# SCH_Flight-Computer-V5_2024-08-18.net
KiCad netlist of a schematic drawn in EasyEDA
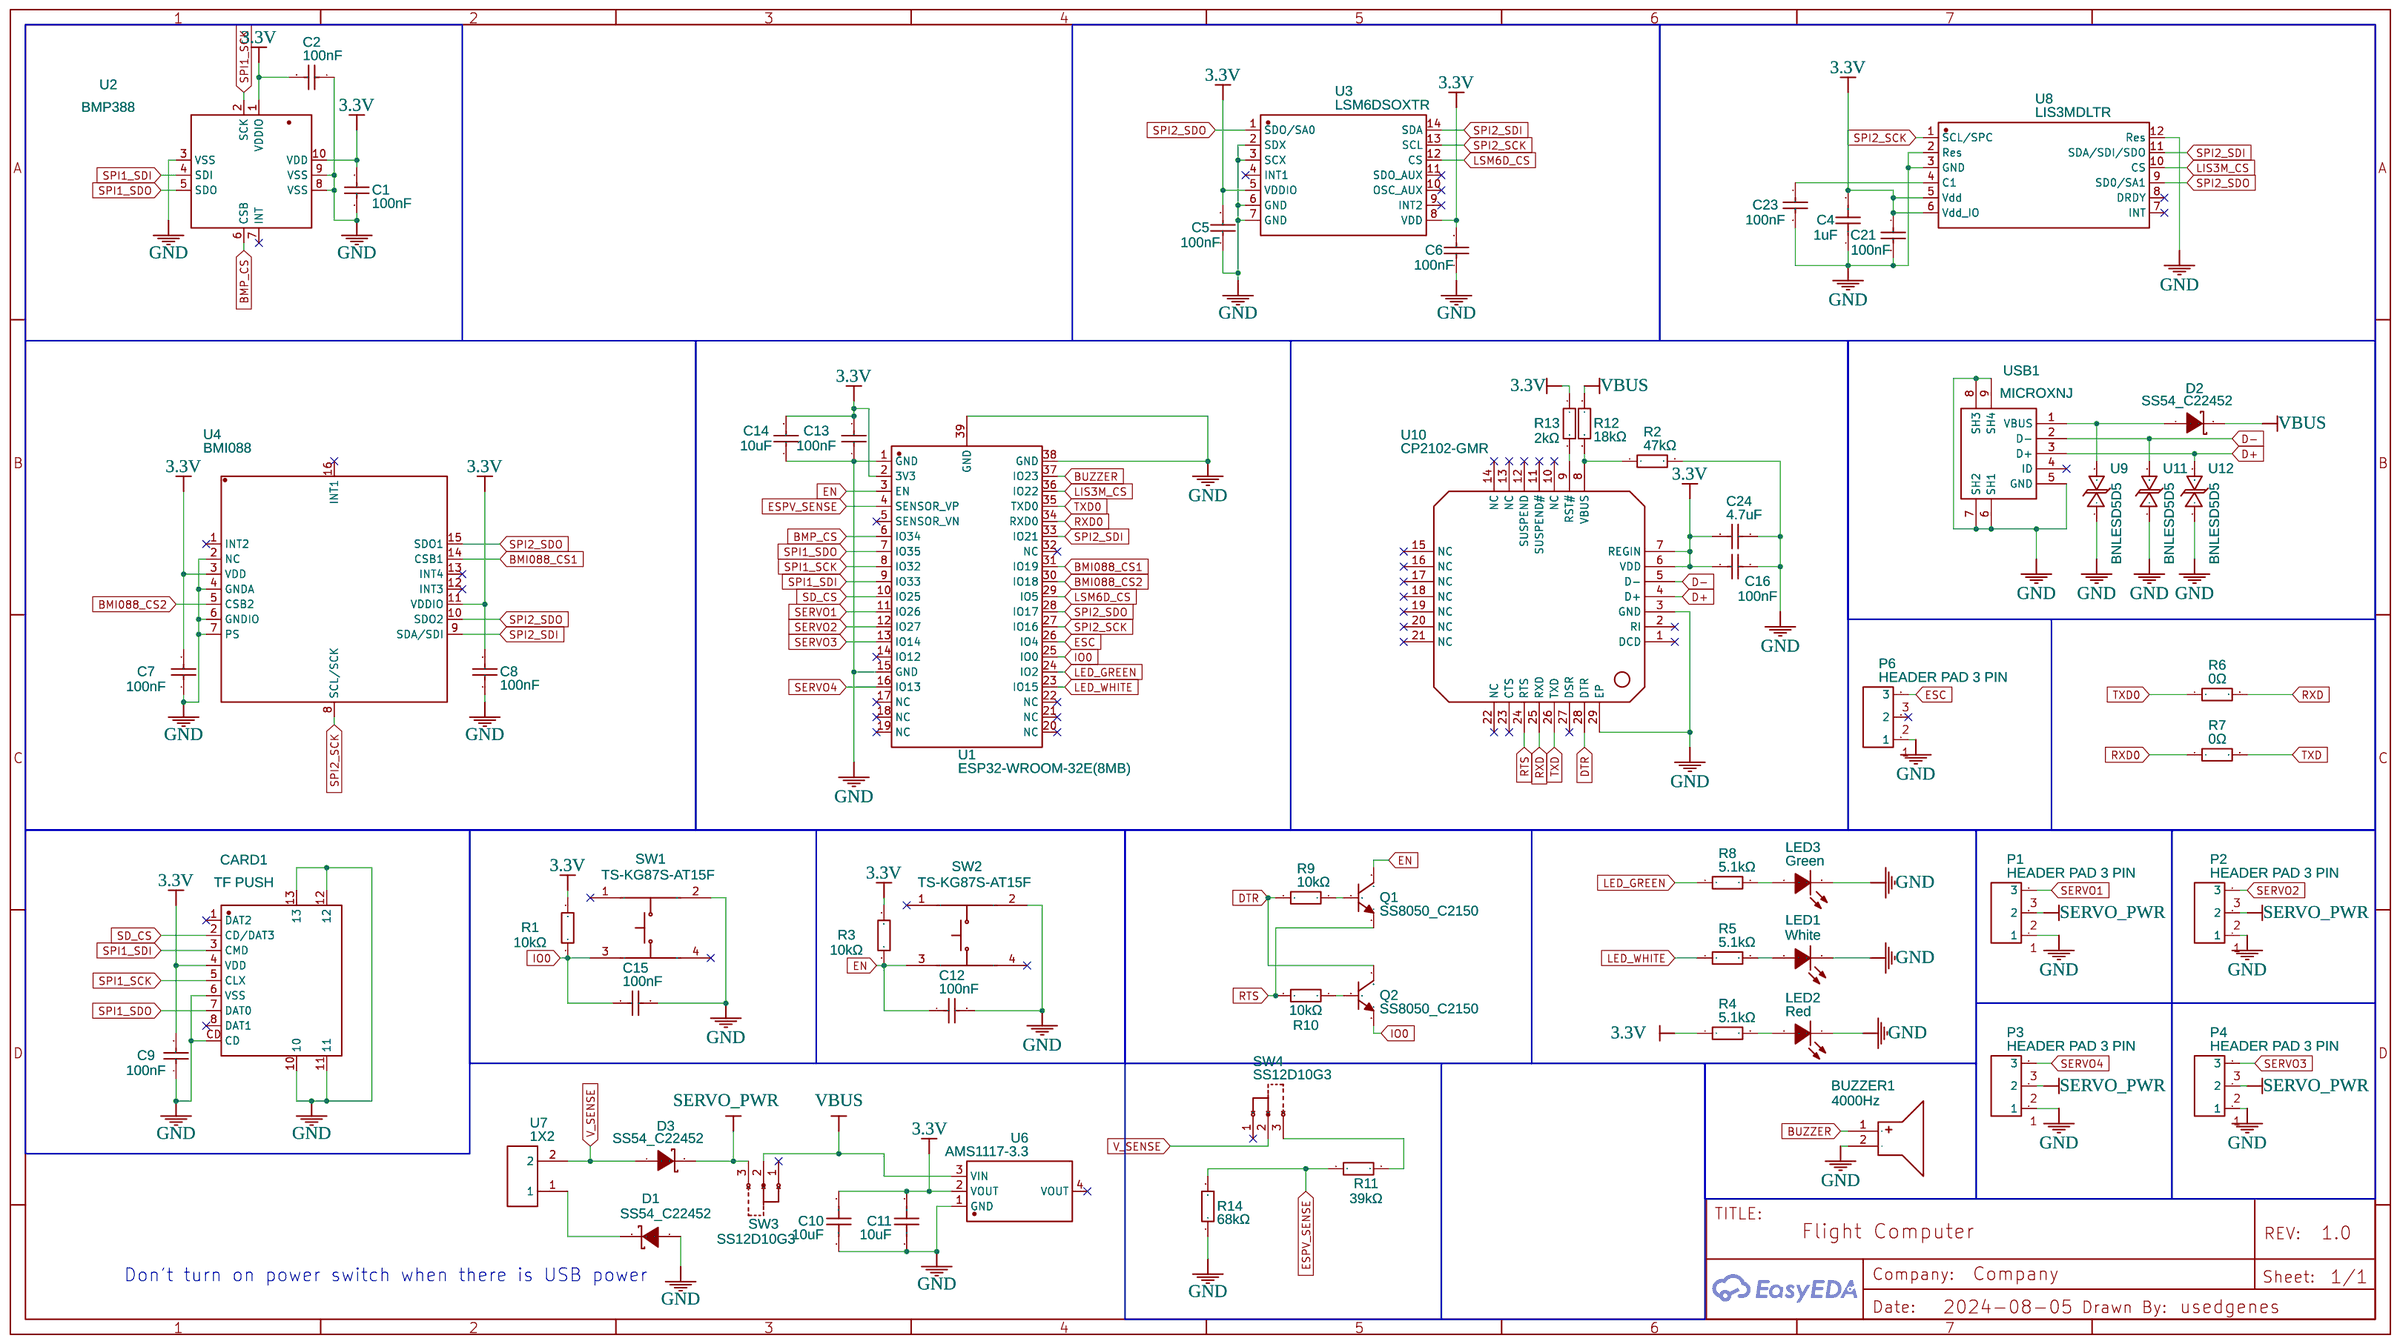
[diagram p0: schematic sheet]

(export (version "E")
  (design (tool "Eeschema 10.0.6"))
  (components
    (comp (ref "BUZZER1")
      (value "4000Hz")
      (fields
        (field (name "Manufacturer Part") "SKY-1475-0540-45P7.6")
        (field (name "Manufacturer") "S&S(海旭)")
      )
      (libsource (lib "") (part "SKY-1475-0540-45P7.6"))
    )
    (comp (ref "C1")
      (value "100nF")
      (fields
        (field (name "Manufacturer Part") "CL05B104KO5NNNC")
        (field (name "Manufacturer") "SAMSUNG(三星)")
      )
      (libsource (lib "") (part "CL05B104KO5NNNC"))
    )
    (comp (ref "C2")
      (value "100nF")
      (fields
        (field (name "Manufacturer Part") "CL05B104KO5NNNC")
        (field (name "Manufacturer") "SAMSUNG(三星)")
      )
      (libsource (lib "") (part "CL05B104KO5NNNC_3"))
    )
    (comp (ref "C4")
      (value "1uF")
      (fields
        (field (name "Manufacturer Part") "CL05A105KA5NQNC")
        (field (name "Manufacturer") "SAMSUNG(三星)")
      )
      (libsource (lib "") (part "CL05A105KA5NQNC"))
    )
    (comp (ref "C5")
      (value "100nF")
      (fields
        (field (name "Manufacturer Part") "CL05B104KO5NNNC")
        (field (name "Manufacturer") "SAMSUNG(三星)")
      )
      (libsource (lib "") (part "CL05B104KO5NNNC"))
    )
    (comp (ref "C6")
      (value "100nF")
      (fields
        (field (name "Manufacturer Part") "CL05B104KO5NNNC")
        (field (name "Manufacturer") "SAMSUNG(三星)")
      )
      (libsource (lib "") (part "CL05B104KO5NNNC"))
    )
    (comp (ref "C7")
      (value "100nF")
      (fields
        (field (name "Manufacturer Part") "CL05B104KO5NNNC")
        (field (name "Manufacturer") "SAMSUNG(三星)")
      )
      (libsource (lib "") (part "CL05B104KO5NNNC"))
    )
    (comp (ref "C8")
      (value "100nF")
      (fields
        (field (name "Manufacturer Part") "CL05B104KO5NNNC")
        (field (name "Manufacturer") "SAMSUNG(三星)")
      )
      (libsource (lib "") (part "CL05B104KO5NNNC"))
    )
    (comp (ref "C9")
      (value "100nF")
      (fields
        (field (name "Manufacturer Part") "CL05B104KO5NNNC")
        (field (name "Manufacturer") "SAMSUNG(三星)")
      )
      (libsource (lib "") (part "CL05B104KO5NNNC"))
    )
    (comp (ref "C10")
      (value "10uF")
      (fields
        (field (name "Manufacturer Part") "CL10A106KP8NNNC")
        (field (name "Manufacturer") "SAMSUNG(三星)")
      )
      (libsource (lib "") (part "CL10A106KP8NNNC"))
    )
    (comp (ref "C11")
      (value "10uF")
      (fields
        (field (name "Manufacturer Part") "CL10A106KP8NNNC")
        (field (name "Manufacturer") "SAMSUNG(三星)")
      )
      (libsource (lib "") (part "CL10A106KP8NNNC"))
    )
    (comp (ref "C12")
      (value "100nF")
      (fields
        (field (name "Manufacturer Part") "CL05B104KO5NNNC")
        (field (name "Manufacturer") "SAMSUNG(三星)")
      )
      (libsource (lib "") (part "CL05B104KO5NNNC_1"))
    )
    (comp (ref "C13")
      (value "100nF")
      (fields
        (field (name "Manufacturer Part") "CL05B104KO5NNNC")
        (field (name "Manufacturer") "SAMSUNG(三星)")
      )
      (libsource (lib "") (part "CL05B104KO5NNNC"))
    )
    (comp (ref "C14")
      (value "10uF")
      (fields
        (field (name "Manufacturer Part") "CL05A106MQ5NUNC")
        (field (name "Manufacturer") "SAMSUNG(三星)")
      )
      (libsource (lib "") (part "CL05A106MQ5NUNC"))
    )
    (comp (ref "C15")
      (value "100nF")
      (fields
        (field (name "Manufacturer Part") "CL05B104KO5NNNC")
        (field (name "Manufacturer") "SAMSUNG(三星)")
      )
      (libsource (lib "") (part "CL05B104KO5NNNC_1"))
    )
    (comp (ref "C16")
      (value "100nF")
      (fields
        (field (name "Manufacturer Part") "CL05B104KO5NNNC")
        (field (name "Manufacturer") "SAMSUNG(三星)")
      )
      (libsource (lib "") (part "CL05B104KO5NNNC_1"))
    )
    (comp (ref "C21")
      (value "100nF")
      (fields
        (field (name "Manufacturer Part") "CL05B104KO5NNNC")
        (field (name "Manufacturer") "SAMSUNG(三星)")
      )
      (libsource (lib "") (part "CL05B104KO5NNNC_2"))
    )
    (comp (ref "C23")
      (value "100nF")
      (fields
        (field (name "Manufacturer Part") "CL05B104KO5NNNC")
        (field (name "Manufacturer") "SAMSUNG(三星)")
      )
      (libsource (lib "") (part "CL05B104KO5NNNC_2"))
    )
    (comp (ref "C24")
      (value "4.7uF")
      (fields
        (field (name "Manufacturer Part") "CL05A475MP5NRNC")
        (field (name "Manufacturer") "SAMSUNG(三星)")
      )
      (libsource (lib "") (part "CL05A475MP5NRNC"))
    )
    (comp (ref "CARD1")
      (value "TF PUSH")
      (fields (field (name "Manufacturer") "SHOU HAN(首韩)"))
      (libsource (lib "") (part "TF PUSH"))
    )
    (comp (ref "D1")
      (value "SS54_C22452")
      (fields (field (name "Manufacturer Part") "SS54") (field (name "Manufacturer") "MDD(辰达半导体)"))
      (libsource (lib "") (part "SS54_C22452_1"))
    )
    (comp (ref "D2")
      (value "SS54_C22452")
      (fields (field (name "Manufacturer Part") "SS54") (field (name "Manufacturer") "MDD(辰达半导体)"))
      (libsource (lib "") (part "SS54_C22452"))
    )
    (comp (ref "D3")
      (value "SS54_C22452")
      (fields (field (name "Manufacturer Part") "SS54") (field (name "Manufacturer") "MDD(辰达半导体)"))
      (libsource (lib "") (part "SS54_C22452"))
    )
    (comp (ref "LED1")
      (value "White")
      (fields (field (name "Manufacturer Part") "KT-0603白灯") (field (name "Manufacturer") "KENTO"))
      (libsource (lib "") (part "0603White light_C2290"))
    )
    (comp (ref "LED2")
      (value "Red")
      (fields (field (name "Manufacturer Part") "KT-0603R") (field (name "Manufacturer") "KENTO"))
      (libsource (lib "") (part "KT-0603R"))
    )
    (comp (ref "LED3")
      (value "Green")
      (fields (field (name "Manufacturer Part") "KT-0805G") (field (name "Manufacturer") "KENTO"))
      (libsource (lib "") (part "0805G (Green)"))
    )
    (comp (ref "P1")
      (value "HEADER PAD 3 PIN")
      (fields
        (field (name "Manufacturer Part") "Female headerHDR1X8-2.54")
        (field (name "Manufacturer") "BOOMELE")
      )
      (libsource (lib "") (part "HEADER PAD 3 PIN"))
    )
    (comp (ref "P2")
      (value "HEADER PAD 3 PIN")
      (fields
        (field (name "Manufacturer Part") "Female headerHDR1X8-2.54")
        (field (name "Manufacturer") "BOOMELE")
      )
      (libsource (lib "") (part "HEADER PAD 3 PIN"))
    )
    (comp (ref "P3")
      (value "HEADER PAD 3 PIN")
      (fields
        (field (name "Manufacturer Part") "Female headerHDR1X8-2.54")
        (field (name "Manufacturer") "BOOMELE")
      )
      (libsource (lib "") (part "HEADER PAD 3 PIN"))
    )
    (comp (ref "P4")
      (value "HEADER PAD 3 PIN")
      (fields
        (field (name "Manufacturer Part") "Female headerHDR1X8-2.54")
        (field (name "Manufacturer") "BOOMELE")
      )
      (libsource (lib "") (part "HEADER PAD 3 PIN"))
    )
    (comp (ref "P6")
      (value "HEADER PAD 3 PIN")
      (fields
        (field (name "Manufacturer Part") "Female headerHDR1X8-2.54")
        (field (name "Manufacturer") "BOOMELE")
      )
      (libsource (lib "") (part "HEADER PAD 3 PIN"))
    )
    (comp (ref "Q1")
      (value "SS8050_C2150")
      (fields (field (name "Manufacturer Part") "SS8050") (field (name "Manufacturer") "CJ(江苏长电/长晶)"))
      (libsource (lib "") (part "SS8050_C2150"))
    )
    (comp (ref "Q2")
      (value "SS8050_C2150")
      (fields (field (name "Manufacturer Part") "SS8050") (field (name "Manufacturer") "CJ(江苏长电/长晶)"))
      (libsource (lib "") (part "SS8050_C2150"))
    )
    (comp (ref "R1")
      (value "10kΩ")
      (fields
        (field (name "Manufacturer Part") "0603WAF1002T5E")
        (field (name "Manufacturer") "UNI-ROYAL(厚声)")
      )
      (libsource (lib "") (part "0603WAF1002T5E_2"))
    )
    (comp (ref "R2")
      (value "47kΩ")
      (fields
        (field (name "Manufacturer Part") "0402WGF4702TCE")
        (field (name "Manufacturer") "UNI-ROYAL(厚声)")
      )
      (libsource (lib "") (part "0402WGF4702TCE"))
    )
    (comp (ref "R3")
      (value "10kΩ")
      (fields
        (field (name "Manufacturer Part") "0603WAF1002T5E")
        (field (name "Manufacturer") "UNI-ROYAL(厚声)")
      )
      (libsource (lib "") (part "0603WAF1002T5E_2"))
    )
    (comp (ref "R4")
      (value "5.1kΩ")
      (fields
        (field (name "Manufacturer Part") "0402WGF5101TCE")
        (field (name "Manufacturer") "UNI-ROYAL(厚声)")
      )
      (libsource (lib "") (part "0402WGF5101TCE"))
    )
    (comp (ref "R5")
      (value "5.1kΩ")
      (fields
        (field (name "Manufacturer Part") "0402WGF5101TCE")
        (field (name "Manufacturer") "UNI-ROYAL(厚声)")
      )
      (libsource (lib "") (part "0402WGF5101TCE"))
    )
    (comp (ref "R6")
      (value "0Ω")
      (fields
        (field (name "Manufacturer Part") "1206W4F0000T5E")
        (field (name "Manufacturer") "UNI-ROYAL(厚声)")
      )
      (libsource (lib "") (part "1206W4F0000T5E"))
    )
    (comp (ref "R7")
      (value "0Ω")
      (fields
        (field (name "Manufacturer Part") "1206W4F0000T5E")
        (field (name "Manufacturer") "UNI-ROYAL(厚声)")
      )
      (libsource (lib "") (part "1206W4F0000T5E"))
    )
    (comp (ref "R8")
      (value "5.1kΩ")
      (fields
        (field (name "Manufacturer Part") "0402WGF5101TCE")
        (field (name "Manufacturer") "UNI-ROYAL(厚声)")
      )
      (libsource (lib "") (part "0402WGF5101TCE"))
    )
    (comp (ref "R9")
      (value "10kΩ")
      (fields
        (field (name "Manufacturer Part") "0603WAF1002T5E")
        (field (name "Manufacturer") "UNI-ROYAL(厚声)")
      )
      (libsource (lib "") (part "0603WAF1002T5E_1"))
    )
    (comp (ref "R10")
      (value "10kΩ")
      (fields
        (field (name "Manufacturer Part") "0603WAF1002T5E")
        (field (name "Manufacturer") "UNI-ROYAL(厚声)")
      )
      (libsource (lib "") (part "0603WAF1002T5E"))
    )
    (comp (ref "R11")
      (value "39kΩ")
      (fields
        (field (name "Manufacturer Part") "0603WAF3902T5E")
        (field (name "Manufacturer") "UNI-ROYAL(厚声)")
      )
      (libsource (lib "") (part "0603WAF3902T5E"))
    )
    (comp (ref "R12")
      (value "18kΩ")
      (fields
        (field (name "Manufacturer Part") "0603WAF1802T5E")
        (field (name "Manufacturer") "UNI-ROYAL(厚声)")
      )
      (libsource (lib "") (part "0603WAF1802T5E"))
    )
    (comp (ref "R13")
      (value "2kΩ")
      (fields
        (field (name "Manufacturer Part") "0402WGF2001TCE")
        (field (name "Manufacturer") "UNI-ROYAL(厚声)")
      )
      (libsource (lib "") (part "0402WGF2001TCE"))
    )
    (comp (ref "R14")
      (value "68kΩ")
      (fields
        (field (name "Manufacturer Part") "0603WAF6802T5E")
        (field (name "Manufacturer") "UNI-ROYAL(厚声)")
      )
      (libsource (lib "") (part "0603WAF6802T5E"))
    )
    (comp (ref "SW1")
      (value "TS-KG87S-AT15F")
      (fields (field (name "Manufacturer") "HANBO(汉博)"))
      (libsource (lib "") (part "TS-KG87S-AT15F"))
    )
    (comp (ref "SW2")
      (value "TS-KG87S-AT15F")
      (fields (field (name "Manufacturer") "HANBO(汉博)"))
      (libsource (lib "") (part "TS-KG87S-AT15F"))
    )
    (comp (ref "SW3")
      (value "SS12D10G3")
      (fields (field (name "Manufacturer") "SHOU HAN(首韩)"))
      (libsource (lib "") (part "SS12D10G3_1"))
    )
    (comp (ref "SW4")
      (value "SS12D10G3")
      (fields (field (name "Manufacturer") "SHOU HAN(首韩)"))
      (libsource (lib "") (part "SS12D10G3"))
    )
    (comp (ref "U1")
      (value "ESP32-WROOM-32E(8MB)")
      (fields
        (field (name "Manufacturer Part") "ESP32-WROOM-32E-N8")
        (field (name "Manufacturer") "ESPRESSIF(乐鑫)")
      )
      (libsource (lib "") (part "ESP32-WROOM-32E(8MB)"))
    )
    (comp (ref "U2")
      (value "BMP388")
      (fields (field (name "Manufacturer") "Bosch(博世)"))
      (libsource (lib "") (part "BMP388"))
    )
    (comp (ref "U3")
      (value "LSM6DSOXTR")
      (fields (field (name "Manufacturer") "ST(意法半导体)"))
      (libsource (lib "") (part "LSM6DSOXTR"))
    )
    (comp (ref "U4")
      (value "BMI088")
      (fields (field (name "Manufacturer") "Bosch(博世)"))
      (libsource (lib "") (part "BMI088"))
    )
    (comp (ref "U6")
      (value "AMS1117-3.3")
      (fields (field (name "Manufacturer") "AMS"))
      (libsource (lib "") (part "AMS1117-3.3"))
    )
    (comp (ref "U7") (value "1X2") (libsource (lib "") (part "1X2")))
    (comp (ref "U8")
      (value "LIS3MDLTR")
      (fields (field (name "Manufacturer") "ST(意法半导体)"))
      (libsource (lib "") (part "LIS3MDLTR"))
    )
    (comp (ref "U9")
      (value "BNLESD5D5")
      (fields
        (field (name "Manufacturer Part") "BNLESD5D5.0CT1G")
        (field (name "Manufacturer") "BORN(伯恩半导体)")
      )
      (libsource (lib "") (part "BNLESD5D5.0CT1G"))
    )
    (comp (ref "U10")
      (value "CP2102-GMR")
      (fields (field (name "Manufacturer") "SKYWORKS/SILICON LABS(芯科)"))
      (libsource (lib "") (part "CP2102-GMR"))
    )
    (comp (ref "U11")
      (value "BNLESD5D5")
      (fields
        (field (name "Manufacturer Part") "BNLESD5D5.0CT1G")
        (field (name "Manufacturer") "BORN(伯恩半导体)")
      )
      (libsource (lib "") (part "BNLESD5D5.0CT1G"))
    )
    (comp (ref "U12")
      (value "BNLESD5D5")
      (fields
        (field (name "Manufacturer Part") "BNLESD5D5.0CT1G")
        (field (name "Manufacturer") "BORN(伯恩半导体)")
      )
      (libsource (lib "") (part "BNLESD5D5.0CT1G"))
    )
    (comp (ref "USB1")
      (value "MICROXNJ")
      (fields (field (name "Manufacturer Part") "MicroXNJ") (field (name "Manufacturer") "SHOU HAN(首韩)"))
      (libsource (lib "") (part "MICROXNJ"))
    )
  )
  (nets
    (net (code "1") (name "3.3V") (class "Default")
      (node (ref "C1") (pin "2") (pinfunction "2_2") (pintype "input"))
      (node (ref "C10") (pin "2") (pinfunction "2_2") (pintype "unspecified"))
      (node (ref "C11") (pin "2") (pinfunction "2_2") (pintype "unspecified"))
      (node (ref "C13") (pin "2") (pinfunction "2_2") (pintype "input"))
      (node (ref "C14") (pin "2") (pinfunction "2_2") (pintype "input"))
      (node (ref "C16") (pin "1") (pinfunction "1_1") (pintype "input"))
      (node (ref "C2") (pin "2") (pinfunction "2_2") (pintype "input"))
      (node (ref "C21") (pin "1") (pinfunction "1_1") (pintype "input"))
      (node (ref "C24") (pin "1") (pinfunction "1_1") (pintype "input"))
      (node (ref "C4") (pin "2") (pinfunction "2_2") (pintype "unspecified"))
      (node (ref "C5") (pin "2") (pinfunction "2_2") (pintype "input"))
      (node (ref "C6") (pin "2") (pinfunction "2_2") (pintype "input"))
      (node (ref "C7") (pin "2") (pinfunction "2_2") (pintype "input"))
      (node (ref "C8") (pin "2") (pinfunction "2_2") (pintype "input"))
      (node (ref "C9") (pin "2") (pinfunction "2_2") (pintype "input"))
      (node (ref "CARD1") (pin "4") (pinfunction "VDD_4") (pintype "unspecified"))
      (node (ref "R1") (pin "2") (pinfunction "2_2") (pintype "input"))
      (node (ref "R13") (pin "1") (pinfunction "1_1") (pintype "input"))
      (node (ref "R3") (pin "2") (pinfunction "2_2") (pintype "input"))
      (node (ref "R4") (pin "1") (pinfunction "1_1") (pintype "input"))
      (node (ref "U1") (pin "2") (pinfunction "3V3_2") (pintype "unspecified"))
      (node (ref "U10") (pin "6") (pinfunction "VDD_6") (pintype "unspecified"))
      (node (ref "U10") (pin "7") (pinfunction "REGIN_7") (pintype "unspecified"))
      (node (ref "U2") (pin "1") (pinfunction "VDDIO_1") (pintype "unspecified"))
      (node (ref "U2") (pin "10") (pinfunction "VDD_10") (pintype "unspecified"))
      (node (ref "U3") (pin "5") (pinfunction "VDDIO_5") (pintype "unspecified"))
      (node (ref "U3") (pin "8") (pinfunction "VDD_8") (pintype "unspecified"))
      (node (ref "U4") (pin "11") (pinfunction "VDDIO_11") (pintype "unspecified"))
      (node (ref "U4") (pin "3") (pinfunction "VDD_3") (pintype "unspecified"))
      (node (ref "U6") (pin "2") (pinfunction "VOUT_2") (pintype "unspecified"))
      (node (ref "U8") (pin "5") (pinfunction "Vdd_5") (pintype "unspecified"))
      (node (ref "U8") (pin "6") (pinfunction "Vdd_IO_6") (pintype "unspecified"))
    )
    (net (code "2") (name "BMI088_CS1") (class "Default")
      (node (ref "U1") (pin "31") (pinfunction "IO19_31") (pintype "unspecified"))
      (node (ref "U4") (pin "14") (pinfunction "CSB1_14") (pintype "unspecified"))
    )
    (net (code "3") (name "BMI088_CS2") (class "Default")
      (node (ref "U1") (pin "30") (pinfunction "IO18_30") (pintype "unspecified"))
      (node (ref "U4") (pin "5") (pinfunction "CSB2_5") (pintype "unspecified"))
    )
    (net (code "4") (name "BMP_CS") (class "Default")
      (node (ref "U1") (pin "6") (pinfunction "IO34_6") (pintype "unspecified"))
      (node (ref "U2") (pin "6") (pinfunction "CSB_6") (pintype "unspecified"))
    )
    (net (code "5") (name "BUZZER") (class "Default")
      (node (ref "BUZZER1") (pin "1") (pinfunction "+_1") (pintype "unspecified"))
      (node (ref "U1") (pin "37") (pinfunction "IO23_37") (pintype "unspecified"))
    )
    (net (code "6") (name "D+") (class "Default")
      (node (ref "U10") (pin "4") (pinfunction "D+_4") (pintype "unspecified"))
      (node (ref "U12") (pin "2") (pinfunction "2_2") (pintype "unspecified"))
      (node (ref "USB1") (pin "3") (pinfunction "D+_3") (pintype "unspecified"))
    )
    (net (code "7") (name "D-") (class "Default")
      (node (ref "U10") (pin "5") (pinfunction "D-_5") (pintype "unspecified"))
      (node (ref "U11") (pin "2") (pinfunction "2_2") (pintype "unspecified"))
      (node (ref "USB1") (pin "2") (pinfunction "D-_2") (pintype "unspecified"))
    )
    (net (code "8") (name "DTR") (class "Default")
      (node (ref "Q2") (pin "3") (pinfunction "C_3") (pintype "unspecified"))
      (node (ref "R9") (pin "2") (pinfunction "2_2") (pintype "input"))
      (node (ref "U10") (pin "28") (pinfunction "DTR_28") (pintype "unspecified"))
    )
    (net (code "9") (name "EN") (class "Default")
      (node (ref "C12") (pin "1") (pinfunction "1_1") (pintype "input"))
      (node (ref "Q1") (pin "3") (pinfunction "C_3") (pintype "unspecified"))
      (node (ref "R3") (pin "1") (pinfunction "1_1") (pintype "input"))
      (node (ref "SW2") (pin "3") (pinfunction "3_3") (pintype "unspecified"))
      (node (ref "U1") (pin "3") (pinfunction "EN_3") (pintype "unspecified"))
    )
    (net (code "10") (name "ESC") (class "Default")
      (node (ref "P6") (pin "3") (pinfunction "3_3") (pintype "unspecified"))
      (node (ref "U1") (pin "26") (pinfunction "IO4_26") (pintype "unspecified"))
    )
    (net (code "11") (name "ESPV_SENSE") (class "Default")
      (node (ref "R11") (pin "1") (pinfunction "1_1") (pintype "input"))
      (node (ref "R14") (pin "2") (pinfunction "2_2") (pintype "input"))
      (node (ref "U1") (pin "4") (pinfunction "SENSOR_VP_4") (pintype "unspecified"))
    )
    (net (code "12") (name "GND") (class "Default")
      (node (ref "BUZZER1") (pin "2") (pinfunction "-_2") (pintype "unspecified"))
      (node (ref "C1") (pin "1") (pinfunction "1_1") (pintype "input"))
      (node (ref "C10") (pin "1") (pinfunction "1_1") (pintype "unspecified"))
      (node (ref "C11") (pin "1") (pinfunction "1_1") (pintype "unspecified"))
      (node (ref "C12") (pin "2") (pinfunction "2_2") (pintype "input"))
      (node (ref "C13") (pin "1") (pinfunction "1_1") (pintype "input"))
      (node (ref "C14") (pin "1") (pinfunction "1_1") (pintype "input"))
      (node (ref "C15") (pin "2") (pinfunction "2_2") (pintype "input"))
      (node (ref "C16") (pin "2") (pinfunction "2_2") (pintype "input"))
      (node (ref "C2") (pin "1") (pinfunction "1_1") (pintype "input"))
      (node (ref "C21") (pin "2") (pinfunction "2_2") (pintype "input"))
      (node (ref "C23") (pin "2") (pinfunction "2_2") (pintype "input"))
      (node (ref "C24") (pin "2") (pinfunction "2_2") (pintype "input"))
      (node (ref "C4") (pin "1") (pinfunction "1_1") (pintype "unspecified"))
      (node (ref "C5") (pin "1") (pinfunction "1_1") (pintype "input"))
      (node (ref "C6") (pin "1") (pinfunction "1_1") (pintype "input"))
      (node (ref "C7") (pin "1") (pinfunction "1_1") (pintype "input"))
      (node (ref "C8") (pin "1") (pinfunction "1_1") (pintype "input"))
      (node (ref "C9") (pin "1") (pinfunction "1_1") (pintype "input"))
      (node (ref "CARD1") (pin "10") (pinfunction "10_10") (pintype "unspecified"))
      (node (ref "CARD1") (pin "11") (pinfunction "11_11") (pintype "unspecified"))
      (node (ref "CARD1") (pin "12") (pinfunction "12_12") (pintype "unspecified"))
      (node (ref "CARD1") (pin "13") (pinfunction "13_13") (pintype "unspecified"))
      (node (ref "CARD1") (pin "6") (pinfunction "VSS_6") (pintype "unspecified"))
      (node (ref "CARD1") (pin "CD") (pinfunction "CD_CD") (pintype "unspecified"))
      (node (ref "D1") (pin "1") (pinfunction "A_1") (pintype "unspecified"))
      (node (ref "LED1") (pin "2") (pinfunction "K_2") (pintype "unspecified"))
      (node (ref "LED2") (pin "1") (pinfunction "K_1") (pintype "unspecified"))
      (node (ref "LED3") (pin "2") (pinfunction "K_2") (pintype "unspecified"))
      (node (ref "P1") (pin "1") (pinfunction "1_1") (pintype "unspecified"))
      (node (ref "P2") (pin "1") (pinfunction "1_1") (pintype "unspecified"))
      (node (ref "P3") (pin "1") (pinfunction "1_1") (pintype "unspecified"))
      (node (ref "P4") (pin "1") (pinfunction "1_1") (pintype "unspecified"))
      (node (ref "P6") (pin "1") (pinfunction "1_1") (pintype "unspecified"))
      (node (ref "R14") (pin "1") (pinfunction "1_1") (pintype "input"))
      (node (ref "R2") (pin "2") (pinfunction "2_2") (pintype "input"))
      (node (ref "SW1") (pin "2") (pinfunction "2_2") (pintype "unspecified"))
      (node (ref "SW2") (pin "2") (pinfunction "2_2") (pintype "unspecified"))
      (node (ref "U1") (pin "1") (pinfunction "GND_1") (pintype "unspecified"))
      (node (ref "U1") (pin "15") (pinfunction "GND_15") (pintype "unspecified"))
      (node (ref "U1") (pin "38") (pinfunction "GND_38") (pintype "unspecified"))
      (node (ref "U1") (pin "39") (pinfunction "GND_39") (pintype "unspecified"))
      (node (ref "U10") (pin "29") (pinfunction "EP_29") (pintype "unspecified"))
      (node (ref "U10") (pin "3") (pinfunction "GND_3") (pintype "unspecified"))
      (node (ref "U11") (pin "1") (pinfunction "1_1") (pintype "unspecified"))
      (node (ref "U12") (pin "1") (pinfunction "1_1") (pintype "unspecified"))
      (node (ref "U2") (pin "3") (pinfunction "VSS_3") (pintype "unspecified"))
      (node (ref "U2") (pin "8") (pinfunction "VSS_8") (pintype "unspecified"))
      (node (ref "U2") (pin "9") (pinfunction "VSS_9") (pintype "unspecified"))
      (node (ref "U3") (pin "2") (pinfunction "SDX_2") (pintype "unspecified"))
      (node (ref "U3") (pin "3") (pinfunction "SCX_3") (pintype "unspecified"))
      (node (ref "U3") (pin "6") (pinfunction "GND_6") (pintype "unspecified"))
      (node (ref "U3") (pin "7") (pinfunction "GND_7") (pintype "unspecified"))
      (node (ref "U4") (pin "2") (pinfunction "NC_2") (pintype "unspecified"))
      (node (ref "U4") (pin "4") (pinfunction "GNDA_4") (pintype "unspecified"))
      (node (ref "U4") (pin "6") (pinfunction "GNDIO_6") (pintype "unspecified"))
      (node (ref "U4") (pin "7") (pinfunction "PS_7") (pintype "unspecified"))
      (node (ref "U6") (pin "1") (pinfunction "GND_1") (pintype "unspecified"))
      (node (ref "U8") (pin "12") (pinfunction "Res_12") (pintype "unspecified"))
      (node (ref "U8") (pin "2") (pinfunction "Res_2") (pintype "unspecified"))
      (node (ref "U8") (pin "3") (pinfunction "GND_3") (pintype "unspecified"))
      (node (ref "U9") (pin "1") (pinfunction "1_1") (pintype "unspecified"))
      (node (ref "USB1") (pin "5") (pinfunction "GND_5") (pintype "unspecified"))
      (node (ref "USB1") (pin "6") (pinfunction "SH1_6") (pintype "unspecified"))
      (node (ref "USB1") (pin "7") (pinfunction "SH2_7") (pintype "unspecified"))
      (node (ref "USB1") (pin "8") (pinfunction "SH3_8") (pintype "unspecified"))
      (node (ref "USB1") (pin "9") (pinfunction "SH4_9") (pintype "unspecified"))
    )
    (net (code "13") (name "IO0") (class "Default")
      (node (ref "C15") (pin "1") (pinfunction "1_1") (pintype "input"))
      (node (ref "Q2") (pin "2") (pinfunction "E_2") (pintype "unspecified"))
      (node (ref "R1") (pin "1") (pinfunction "1_1") (pintype "input"))
      (node (ref "SW1") (pin "3") (pinfunction "3_3") (pintype "unspecified"))
      (node (ref "U1") (pin "25") (pinfunction "IO0_25") (pintype "unspecified"))
    )
    (net (code "14") (name "LED_GREEN") (class "Default")
      (node (ref "R8") (pin "1") (pinfunction "1_1") (pintype "input"))
      (node (ref "U1") (pin "24") (pinfunction "IO2_24") (pintype "unspecified"))
    )
    (net (code "15") (name "LED_WHITE") (class "Default")
      (node (ref "R5") (pin "1") (pinfunction "1_1") (pintype "input"))
      (node (ref "U1") (pin "23") (pinfunction "IO15_23") (pintype "unspecified"))
    )
    (net (code "16") (name "LIS3M_CS") (class "Default")
      (node (ref "U1") (pin "36") (pinfunction "IO22_36") (pintype "unspecified"))
      (node (ref "U8") (pin "10") (pinfunction "CS_10") (pintype "unspecified"))
    )
    (net (code "17") (name "LSM6D_CS") (class "Default")
      (node (ref "U1") (pin "29") (pinfunction "IO5_29") (pintype "unspecified"))
      (node (ref "U3") (pin "12") (pinfunction "CS_12") (pintype "unspecified"))
    )
    (net (code "18") (name "Net-(D1-K)") (class "Default")
      (node (ref "D1") (pin "2") (pinfunction "K_2") (pintype "unspecified"))
      (node (ref "U7") (pin "1") (pinfunction "1_1") (pintype "unspecified"))
    )
    (net (code "19") (name "Net-(D2-A)") (class "Default")
      (node (ref "D2") (pin "1") (pinfunction "A_1") (pintype "unspecified"))
      (node (ref "U9") (pin "2") (pinfunction "2_2") (pintype "unspecified"))
      (node (ref "USB1") (pin "1") (pinfunction "VBUS_1") (pintype "unspecified"))
    )
    (net (code "20") (name "Net-(LED1-A)") (class "Default")
      (node (ref "LED1") (pin "1") (pinfunction "A_1") (pintype "unspecified"))
      (node (ref "R5") (pin "2") (pinfunction "2_2") (pintype "input"))
    )
    (net (code "21") (name "Net-(LED2-A)") (class "Default")
      (node (ref "LED2") (pin "2") (pinfunction "A_2") (pintype "unspecified"))
      (node (ref "R4") (pin "2") (pinfunction "2_2") (pintype "input"))
    )
    (net (code "22") (name "Net-(LED3-A)") (class "Default")
      (node (ref "LED3") (pin "1") (pinfunction "A_1") (pintype "unspecified"))
      (node (ref "R8") (pin "2") (pinfunction "2_2") (pintype "input"))
    )
    (net (code "23") (name "Net-(Q1-B)") (class "Default")
      (node (ref "Q1") (pin "1") (pinfunction "B_1") (pintype "unspecified"))
      (node (ref "R9") (pin "1") (pinfunction "1_1") (pintype "input"))
    )
    (net (code "24") (name "Net-(Q2-B)") (class "Default")
      (node (ref "Q2") (pin "1") (pinfunction "B_1") (pintype "unspecified"))
      (node (ref "R10") (pin "2") (pinfunction "2_2") (pintype "input"))
    )
    (net (code "25") (name "Net-(R11-Pad2)") (class "Default")
      (node (ref "R11") (pin "2") (pinfunction "2_2") (pintype "input"))
      (node (ref "SW4") (pin "3") (pinfunction "3_3") (pintype "unspecified"))
    )
    (net (code "26") (name "Net-(U8-C1)") (class "Default")
      (node (ref "C23") (pin "1") (pinfunction "1_1") (pintype "input"))
      (node (ref "U8") (pin "4") (pinfunction "C1_4") (pintype "unspecified"))
    )
    (net (code "27") (name "Net-(U10-RST#)") (class "Default")
      (node (ref "R13") (pin "2") (pinfunction "2_2") (pintype "input"))
      (node (ref "U10") (pin "9") (pinfunction "RST#_9") (pintype "unspecified"))
    )
    (net (code "28") (name "Net-(U10-VBUS)") (class "Default")
      (node (ref "R12") (pin "2") (pinfunction "2_2") (pintype "input"))
      (node (ref "R2") (pin "1") (pinfunction "1_1") (pintype "input"))
      (node (ref "U10") (pin "8") (pinfunction "VBUS_8") (pintype "unspecified"))
    )
    (net (code "29") (name "RTS") (class "Default")
      (node (ref "Q1") (pin "2") (pinfunction "E_2") (pintype "unspecified"))
      (node (ref "R10") (pin "1") (pinfunction "1_1") (pintype "input"))
      (node (ref "U10") (pin "24") (pinfunction "RTS_24") (pintype "unspecified"))
    )
    (net (code "30") (name "RXD") (class "Default")
      (node (ref "R6") (pin "2") (pinfunction "2_2") (pintype "input"))
      (node (ref "U10") (pin "25") (pinfunction "RXD_25") (pintype "unspecified"))
    )
    (net (code "31") (name "RXD0") (class "Default")
      (node (ref "R7") (pin "1") (pinfunction "1_1") (pintype "input"))
      (node (ref "U1") (pin "34") (pinfunction "RXD0_34") (pintype "unspecified"))
    )
    (net (code "32") (name "SD_CS") (class "Default")
      (node (ref "CARD1") (pin "2") (pinfunction "CD/DAT3_2") (pintype "unspecified"))
      (node (ref "U1") (pin "10") (pinfunction "IO25_10") (pintype "unspecified"))
    )
    (net (code "33") (name "SERVO1") (class "Default")
      (node (ref "P1") (pin "3") (pinfunction "3_3") (pintype "unspecified"))
      (node (ref "U1") (pin "11") (pinfunction "IO26_11") (pintype "unspecified"))
    )
    (net (code "34") (name "SERVO2") (class "Default")
      (node (ref "P2") (pin "3") (pinfunction "3_3") (pintype "unspecified"))
      (node (ref "U1") (pin "12") (pinfunction "IO27_12") (pintype "unspecified"))
    )
    (net (code "35") (name "SERVO3") (class "Default")
      (node (ref "P4") (pin "3") (pinfunction "3_3") (pintype "unspecified"))
      (node (ref "U1") (pin "13") (pinfunction "IO14_13") (pintype "unspecified"))
    )
    (net (code "36") (name "SERVO4") (class "Default")
      (node (ref "P3") (pin "3") (pinfunction "3_3") (pintype "unspecified"))
      (node (ref "U1") (pin "16") (pinfunction "IO13_16") (pintype "unspecified"))
    )
    (net (code "37") (name "SERVO_PWR") (class "Default")
      (node (ref "D3") (pin "2") (pinfunction "K_2") (pintype "unspecified"))
      (node (ref "P1") (pin "2") (pinfunction "2_2") (pintype "unspecified"))
      (node (ref "P2") (pin "2") (pinfunction "2_2") (pintype "unspecified"))
      (node (ref "P3") (pin "2") (pinfunction "2_2") (pintype "unspecified"))
      (node (ref "P4") (pin "2") (pinfunction "2_2") (pintype "unspecified"))
      (node (ref "SW3") (pin "3") (pinfunction "3_3") (pintype "unspecified"))
    )
    (net (code "38") (name "SPI1_SCK") (class "Default")
      (node (ref "CARD1") (pin "5") (pinfunction "CLX_5") (pintype "unspecified"))
      (node (ref "U1") (pin "8") (pinfunction "IO32_8") (pintype "unspecified"))
      (node (ref "U2") (pin "2") (pinfunction "SCK_2") (pintype "unspecified"))
    )
    (net (code "39") (name "SPI1_SDI") (class "Default")
      (node (ref "CARD1") (pin "3") (pinfunction "CMD_3") (pintype "unspecified"))
      (node (ref "U1") (pin "9") (pinfunction "IO33_9") (pintype "unspecified"))
      (node (ref "U2") (pin "4") (pinfunction "SDI_4") (pintype "unspecified"))
    )
    (net (code "40") (name "SPI1_SDO") (class "Default")
      (node (ref "CARD1") (pin "7") (pinfunction "DAT0_7") (pintype "unspecified"))
      (node (ref "U1") (pin "7") (pinfunction "IO35_7") (pintype "unspecified"))
      (node (ref "U2") (pin "5") (pinfunction "SDO_5") (pintype "unspecified"))
    )
    (net (code "41") (name "SPI2_SCK") (class "Default")
      (node (ref "U1") (pin "27") (pinfunction "IO16_27") (pintype "unspecified"))
      (node (ref "U3") (pin "13") (pinfunction "SCL_13") (pintype "unspecified"))
      (node (ref "U4") (pin "8") (pinfunction "SCL/SCK_8") (pintype "unspecified"))
      (node (ref "U8") (pin "1") (pinfunction "SCL/SPC_1") (pintype "unspecified"))
    )
    (net (code "42") (name "SPI2_SDI") (class "Default")
      (node (ref "U1") (pin "33") (pinfunction "IO21_33") (pintype "unspecified"))
      (node (ref "U3") (pin "14") (pinfunction "SDA_14") (pintype "unspecified"))
      (node (ref "U4") (pin "9") (pinfunction "SDA/SDI_9") (pintype "unspecified"))
      (node (ref "U8") (pin "11") (pinfunction "SDA/SDI/SDO_11") (pintype "unspecified"))
    )
    (net (code "43") (name "SPI2_SDO") (class "Default")
      (node (ref "U1") (pin "28") (pinfunction "IO17_28") (pintype "unspecified"))
      (node (ref "U3") (pin "1") (pinfunction "SDO/SA0_1") (pintype "unspecified"))
      (node (ref "U4") (pin "10") (pinfunction "SDO2_10") (pintype "unspecified"))
      (node (ref "U4") (pin "15") (pinfunction "SDO1_15") (pintype "unspecified"))
      (node (ref "U8") (pin "9") (pinfunction "SD0/SA1_9") (pintype "unspecified"))
    )
    (net (code "44") (name "TXD") (class "Default")
      (node (ref "R7") (pin "2") (pinfunction "2_2") (pintype "input"))
      (node (ref "U10") (pin "26") (pinfunction "TXD_26") (pintype "unspecified"))
    )
    (net (code "45") (name "TXD0") (class "Default")
      (node (ref "R6") (pin "1") (pinfunction "1_1") (pintype "input"))
      (node (ref "U1") (pin "35") (pinfunction "TXD0_35") (pintype "unspecified"))
    )
    (net (code "46") (name "VBUS") (class "Default")
      (node (ref "D2") (pin "2") (pinfunction "K_2") (pintype "unspecified"))
      (node (ref "R12") (pin "1") (pinfunction "1_1") (pintype "input"))
      (node (ref "SW3") (pin "2") (pinfunction "2_2") (pintype "unspecified"))
      (node (ref "U6") (pin "3") (pinfunction "VIN_3") (pintype "unspecified"))
    )
    (net (code "47") (name "V_SENSE") (class "Default")
      (node (ref "D3") (pin "1") (pinfunction "A_1") (pintype "unspecified"))
      (node (ref "SW4") (pin "2") (pinfunction "2_2") (pintype "unspecified"))
      (node (ref "U7") (pin "2") (pinfunction "2_2") (pintype "unspecified"))
    )
    (net (code "48") (name "unconnected-(CARD1-DAT1-Pad8)") (class "Default")
      (node (ref "CARD1") (pin "8") (pinfunction "DAT1_8") (pintype "unspecified+no_connect"))
    )
    (net (code "49") (name "unconnected-(CARD1-DAT2-Pad1)") (class "Default")
      (node (ref "CARD1") (pin "1") (pinfunction "DAT2_1") (pintype "unspecified+no_connect"))
    )
    (net (code "50") (name "unconnected-(P6-Pad2)") (class "Default")
      (node (ref "P6") (pin "2") (pinfunction "2_2") (pintype "unspecified+no_connect"))
    )
    (net (code "51") (name "unconnected-(SW1-Pad1)") (class "Default")
      (node (ref "SW1") (pin "1") (pinfunction "1_1") (pintype "unspecified+no_connect"))
    )
    (net (code "52") (name "unconnected-(SW1-Pad4)") (class "Default")
      (node (ref "SW1") (pin "4") (pinfunction "4_4") (pintype "unspecified+no_connect"))
    )
    (net (code "53") (name "unconnected-(SW2-Pad1)") (class "Default")
      (node (ref "SW2") (pin "1") (pinfunction "1_1") (pintype "unspecified+no_connect"))
    )
    (net (code "54") (name "unconnected-(SW2-Pad4)") (class "Default")
      (node (ref "SW2") (pin "4") (pinfunction "4_4") (pintype "unspecified+no_connect"))
    )
    (net (code "55") (name "unconnected-(SW3-Pad1)") (class "Default")
      (node (ref "SW3") (pin "1") (pinfunction "1_1") (pintype "unspecified+no_connect"))
    )
    (net (code "56") (name "unconnected-(SW4-Pad1)") (class "Default")
      (node (ref "SW4") (pin "1") (pinfunction "1_1") (pintype "unspecified+no_connect"))
    )
    (net (code "57") (name "unconnected-(U1-IO12-Pad14)") (class "Default")
      (node (ref "U1") (pin "14") (pinfunction "IO12_14") (pintype "unspecified+no_connect"))
    )
    (net (code "58") (name "unconnected-(U1-NC-Pad17)") (class "Default")
      (node (ref "U1") (pin "17") (pinfunction "NC_17") (pintype "unspecified+no_connect"))
    )
    (net (code "59") (name "unconnected-(U1-NC-Pad18)") (class "Default")
      (node (ref "U1") (pin "18") (pinfunction "NC_18") (pintype "unspecified+no_connect"))
    )
    (net (code "60") (name "unconnected-(U1-NC-Pad19)") (class "Default")
      (node (ref "U1") (pin "19") (pinfunction "NC_19") (pintype "unspecified+no_connect"))
    )
    (net (code "61") (name "unconnected-(U1-NC-Pad20)") (class "Default")
      (node (ref "U1") (pin "20") (pinfunction "NC_20") (pintype "unspecified+no_connect"))
    )
    (net (code "62") (name "unconnected-(U1-NC-Pad21)") (class "Default")
      (node (ref "U1") (pin "21") (pinfunction "NC_21") (pintype "unspecified+no_connect"))
    )
    (net (code "63") (name "unconnected-(U1-NC-Pad22)") (class "Default")
      (node (ref "U1") (pin "22") (pinfunction "NC_22") (pintype "unspecified+no_connect"))
    )
    (net (code "64") (name "unconnected-(U1-NC-Pad32)") (class "Default")
      (node (ref "U1") (pin "32") (pinfunction "NC_32") (pintype "unspecified+no_connect"))
    )
    (net (code "65") (name "unconnected-(U1-SENSOR_VN-Pad5)") (class "Default")
      (node (ref "U1") (pin "5") (pinfunction "SENSOR_VN_5") (pintype "unspecified+no_connect"))
    )
    (net (code "66") (name "unconnected-(U2-INT-Pad7)") (class "Default")
      (node (ref "U2") (pin "7") (pinfunction "INT_7") (pintype "unspecified+no_connect"))
    )
    (net (code "67") (name "unconnected-(U3-INT1-Pad4)") (class "Default")
      (node (ref "U3") (pin "4") (pinfunction "INT1_4") (pintype "unspecified+no_connect"))
    )
    (net (code "68") (name "unconnected-(U3-INT2-Pad9)") (class "Default")
      (node (ref "U3") (pin "9") (pinfunction "INT2_9") (pintype "unspecified+no_connect"))
    )
    (net (code "69") (name "unconnected-(U3-OSC_AUX-Pad10)") (class "Default")
      (node (ref "U3") (pin "10") (pinfunction "OSC_AUX_10") (pintype "unspecified+no_connect"))
    )
    (net (code "70") (name "unconnected-(U3-SDO_AUX-Pad11)") (class "Default")
      (node (ref "U3") (pin "11") (pinfunction "SDO_AUX_11") (pintype "unspecified+no_connect"))
    )
    (net (code "71") (name "unconnected-(U4-INT1-Pad16)") (class "Default")
      (node (ref "U4") (pin "16") (pinfunction "INT1_16") (pintype "unspecified+no_connect"))
    )
    (net (code "72") (name "unconnected-(U4-INT2-Pad1)") (class "Default")
      (node (ref "U4") (pin "1") (pinfunction "INT2_1") (pintype "unspecified+no_connect"))
    )
    (net (code "73") (name "unconnected-(U4-INT3-Pad12)") (class "Default")
      (node (ref "U4") (pin "12") (pinfunction "INT3_12") (pintype "unspecified+no_connect"))
    )
    (net (code "74") (name "unconnected-(U4-INT4-Pad13)") (class "Default")
      (node (ref "U4") (pin "13") (pinfunction "INT4_13") (pintype "unspecified+no_connect"))
    )
    (net (code "75") (name "unconnected-(U6-VOUT-Pad4)") (class "Default")
      (node (ref "U6") (pin "4") (pinfunction "VOUT_4") (pintype "unspecified+no_connect"))
    )
    (net (code "76") (name "unconnected-(U8-DRDY-Pad8)") (class "Default")
      (node (ref "U8") (pin "8") (pinfunction "DRDY_8") (pintype "unspecified+no_connect"))
    )
    (net (code "77") (name "unconnected-(U8-INT-Pad7)") (class "Default")
      (node (ref "U8") (pin "7") (pinfunction "INT_7") (pintype "unspecified+no_connect"))
    )
    (net (code "78") (name "unconnected-(U10-CTS-Pad23)") (class "Default")
      (node (ref "U10") (pin "23") (pinfunction "CTS_23") (pintype "unspecified+no_connect"))
    )
    (net (code "79") (name "unconnected-(U10-DCD-Pad1)") (class "Default")
      (node (ref "U10") (pin "1") (pinfunction "DCD_1") (pintype "unspecified+no_connect"))
    )
    (net (code "80") (name "unconnected-(U10-DSR-Pad27)") (class "Default")
      (node (ref "U10") (pin "27") (pinfunction "DSR_27") (pintype "unspecified+no_connect"))
    )
    (net (code "81") (name "unconnected-(U10-NC-Pad10)") (class "Default")
      (node (ref "U10") (pin "10") (pinfunction "NC_10") (pintype "unspecified+no_connect"))
    )
    (net (code "82") (name "unconnected-(U10-NC-Pad13)") (class "Default")
      (node (ref "U10") (pin "13") (pinfunction "NC_13") (pintype "unspecified+no_connect"))
    )
    (net (code "83") (name "unconnected-(U10-NC-Pad14)") (class "Default")
      (node (ref "U10") (pin "14") (pinfunction "NC_14") (pintype "unspecified+no_connect"))
    )
    (net (code "84") (name "unconnected-(U10-NC-Pad15)") (class "Default")
      (node (ref "U10") (pin "15") (pinfunction "NC_15") (pintype "unspecified+no_connect"))
    )
    (net (code "85") (name "unconnected-(U10-NC-Pad16)") (class "Default")
      (node (ref "U10") (pin "16") (pinfunction "NC_16") (pintype "unspecified+no_connect"))
    )
    (net (code "86") (name "unconnected-(U10-NC-Pad17)") (class "Default")
      (node (ref "U10") (pin "17") (pinfunction "NC_17") (pintype "unspecified+no_connect"))
    )
    (net (code "87") (name "unconnected-(U10-NC-Pad18)") (class "Default")
      (node (ref "U10") (pin "18") (pinfunction "NC_18") (pintype "unspecified+no_connect"))
    )
    (net (code "88") (name "unconnected-(U10-NC-Pad19)") (class "Default")
      (node (ref "U10") (pin "19") (pinfunction "NC_19") (pintype "unspecified+no_connect"))
    )
    (net (code "89") (name "unconnected-(U10-NC-Pad20)") (class "Default")
      (node (ref "U10") (pin "20") (pinfunction "NC_20") (pintype "unspecified+no_connect"))
    )
    (net (code "90") (name "unconnected-(U10-NC-Pad21)") (class "Default")
      (node (ref "U10") (pin "21") (pinfunction "NC_21") (pintype "unspecified+no_connect"))
    )
    (net (code "91") (name "unconnected-(U10-NC-Pad22)") (class "Default")
      (node (ref "U10") (pin "22") (pinfunction "NC_22") (pintype "unspecified+no_connect"))
    )
    (net (code "92") (name "unconnected-(U10-RI-Pad2)") (class "Default")
      (node (ref "U10") (pin "2") (pinfunction "RI_2") (pintype "unspecified+no_connect"))
    )
    (net (code "93") (name "unconnected-(U10-SUSPEND#-Pad11)") (class "Default")
      (node (ref "U10") (pin "11") (pinfunction "SUSPEND#_11") (pintype "unspecified+no_connect"))
    )
    (net (code "94") (name "unconnected-(U10-SUSPEND-Pad12)") (class "Default")
      (node (ref "U10") (pin "12") (pinfunction "SUSPEND_12") (pintype "unspecified+no_connect"))
    )
    (net (code "95") (name "unconnected-(USB1-ID-Pad4)") (class "Default")
      (node (ref "USB1") (pin "4") (pinfunction "ID_4") (pintype "unspecified+no_connect"))
    )
  )
)
